# SimpleLedEgg.net
KiCad netlist of a schematic drawn in EAGLE
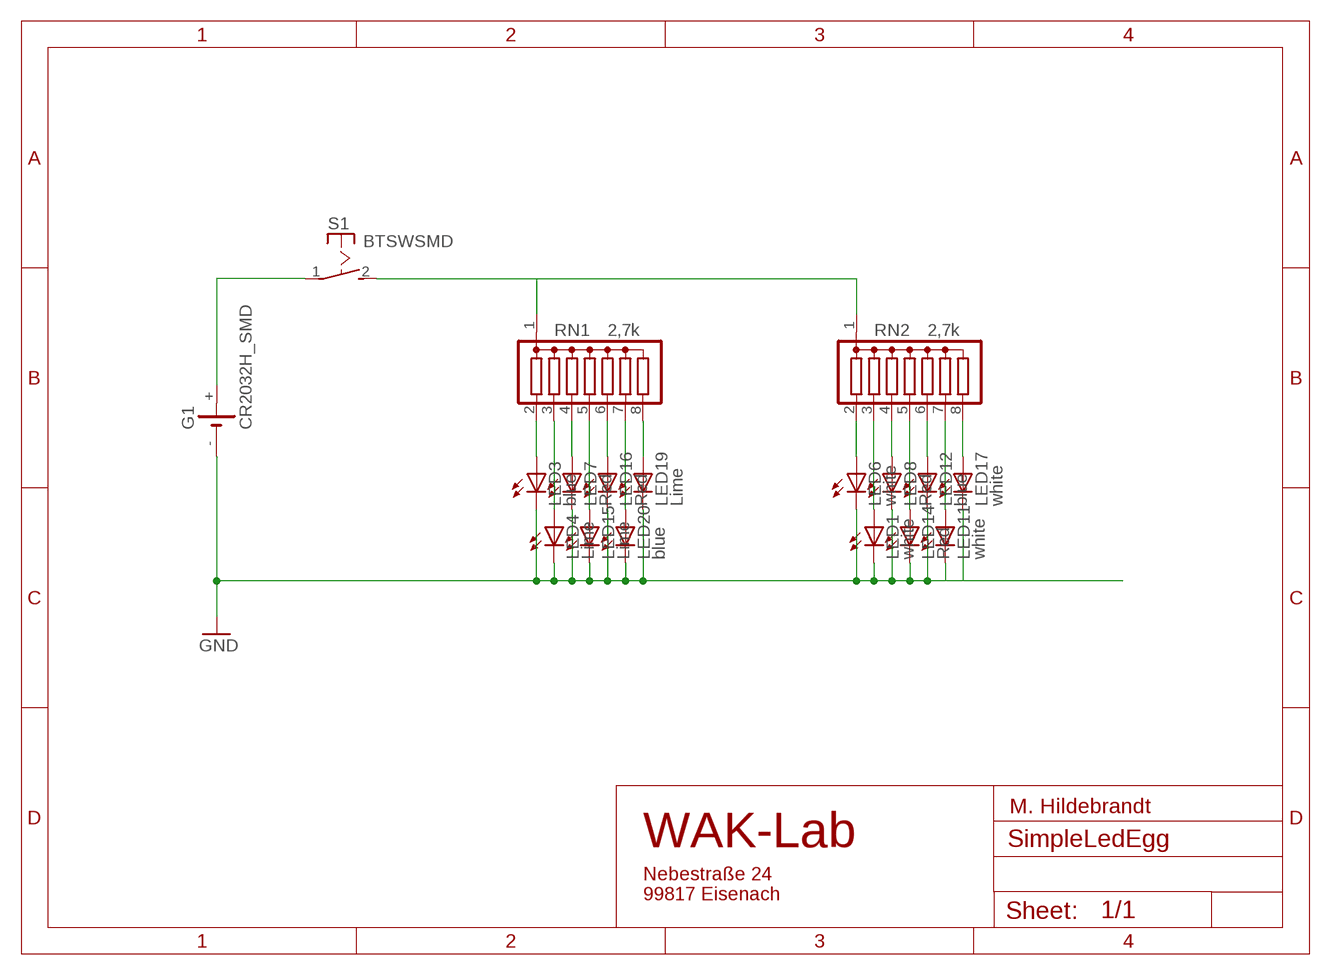
[diagram p0: schematic, sheet 1]

(export (version "E")
  (design (tool "Eeschema 10.0.6"))
  (components
    (comp (ref "G1")
      (value "CR2032H_SMD")
      (footprint "eagle-import:CR2032H_SMD")
      (libsource (lib "eagle-import") (part "CR2032H_SMD"))
    )
    (comp (ref "LED1")
      (value "white")
      (footprint "eagle-import:LED3MM")
      (libsource (lib "eagle-import") (part "LED3MM"))
    )
    (comp (ref "LED3")
      (value "blue")
      (footprint "eagle-import:LED3MM")
      (libsource (lib "eagle-import") (part "LED3MM"))
    )
    (comp (ref "LED4")
      (value "Lime")
      (footprint "eagle-import:LED3MM")
      (libsource (lib "eagle-import") (part "LED3MM"))
    )
    (comp (ref "LED6")
      (value "white")
      (footprint "eagle-import:LED3MM")
      (libsource (lib "eagle-import") (part "LED3MM"))
    )
    (comp (ref "LED7")
      (value "Red")
      (footprint "eagle-import:LED3MM")
      (libsource (lib "eagle-import") (part "LED3MM"))
    )
    (comp (ref "LED8")
      (value "Red")
      (footprint "eagle-import:LED3MM")
      (libsource (lib "eagle-import") (part "LED3MM"))
    )
    (comp (ref "LED11")
      (value "white")
      (footprint "eagle-import:LED3MM")
      (libsource (lib "eagle-import") (part "LED3MM"))
    )
    (comp (ref "LED12")
      (value "blue")
      (footprint "eagle-import:LED3MM")
      (libsource (lib "eagle-import") (part "LED3MM"))
    )
    (comp (ref "LED14")
      (value "Red")
      (footprint "eagle-import:LED3MM")
      (libsource (lib "eagle-import") (part "LED3MM"))
    )
    (comp (ref "LED15")
      (value "Lime")
      (footprint "eagle-import:LED3MM")
      (libsource (lib "eagle-import") (part "LED3MM"))
    )
    (comp (ref "LED16")
      (value "Red")
      (footprint "eagle-import:LED3MM")
      (libsource (lib "eagle-import") (part "LED3MM"))
    )
    (comp (ref "LED17")
      (value "white")
      (footprint "eagle-import:LED3MM")
      (libsource (lib "eagle-import") (part "LED3MM"))
    )
    (comp (ref "LED19")
      (value "Lime")
      (footprint "eagle-import:LED3MM")
      (libsource (lib "eagle-import") (part "LED3MM"))
    )
    (comp (ref "LED20")
      (value "blue")
      (footprint "eagle-import:LED3MM")
      (libsource (lib "eagle-import") (part "LED3MM"))
    )
    (comp (ref "RN1")
      (value "2,7k")
      (footprint "eagle-import:SIL8")
      (libsource (lib "eagle-import") (part "G07R"))
    )
    (comp (ref "RN2")
      (value "2,7k")
      (footprint "eagle-import:SIL8")
      (libsource (lib "eagle-import") (part "G07R"))
    )
    (comp (ref "S1")
      (value "BTSWSMD")
      (footprint "eagle-import:BTSW_SMD")
      (libsource (lib "eagle-import") (part "BTSWSMD"))
    )
  )
  (nets
    (net (code "1") (name "GND") (class "Default")
      (node (ref "G1") (pin "-") (pinfunction "-_-") (pintype "passive"))
      (node (ref "LED1") (pin "K") (pinfunction "C_K") (pintype "passive"))
      (node (ref "LED11") (pin "K") (pinfunction "C_K") (pintype "passive"))
      (node (ref "LED12") (pin "K") (pinfunction "C_K") (pintype "passive"))
      (node (ref "LED14") (pin "K") (pinfunction "C_K") (pintype "passive"))
      (node (ref "LED15") (pin "K") (pinfunction "C_K") (pintype "passive"))
      (node (ref "LED16") (pin "K") (pinfunction "C_K") (pintype "passive"))
      (node (ref "LED17") (pin "K") (pinfunction "C_K") (pintype "passive"))
      (node (ref "LED19") (pin "K") (pinfunction "C_K") (pintype "passive"))
      (node (ref "LED20") (pin "K") (pinfunction "C_K") (pintype "passive"))
      (node (ref "LED3") (pin "K") (pinfunction "C_K") (pintype "passive"))
      (node (ref "LED4") (pin "K") (pinfunction "C_K") (pintype "passive"))
      (node (ref "LED6") (pin "K") (pinfunction "C_K") (pintype "passive"))
      (node (ref "LED7") (pin "K") (pinfunction "C_K") (pintype "passive"))
      (node (ref "LED8") (pin "K") (pinfunction "C_K") (pintype "passive"))
    )
    (net (code "2") (name "Net-(LED1-PadA)") (class "Default")
      (node (ref "LED1") (pin "A") (pinfunction "A_A") (pintype "passive"))
      (node (ref "RN2") (pin "3") (pinfunction "3_3") (pintype "passive"))
    )
    (net (code "3") (name "Net-(LED3-PadA)") (class "Default")
      (node (ref "LED3") (pin "A") (pinfunction "A_A") (pintype "passive"))
      (node (ref "RN1") (pin "2") (pinfunction "2_2") (pintype "passive"))
    )
    (net (code "4") (name "Net-(LED4-PadA)") (class "Default")
      (node (ref "LED4") (pin "A") (pinfunction "A_A") (pintype "passive"))
      (node (ref "RN1") (pin "3") (pinfunction "3_3") (pintype "passive"))
    )
    (net (code "5") (name "Net-(LED6-PadA)") (class "Default")
      (node (ref "LED6") (pin "A") (pinfunction "A_A") (pintype "passive"))
      (node (ref "RN2") (pin "2") (pinfunction "2_2") (pintype "passive"))
    )
    (net (code "6") (name "Net-(LED7-PadA)") (class "Default")
      (node (ref "LED7") (pin "A") (pinfunction "A_A") (pintype "passive"))
      (node (ref "RN1") (pin "4") (pinfunction "4_4") (pintype "passive"))
    )
    (net (code "7") (name "Net-(LED8-PadA)") (class "Default")
      (node (ref "LED8") (pin "A") (pinfunction "A_A") (pintype "passive"))
      (node (ref "RN2") (pin "4") (pinfunction "4_4") (pintype "passive"))
    )
    (net (code "8") (name "Net-(LED11-PadA)") (class "Default")
      (node (ref "LED11") (pin "A") (pinfunction "A_A") (pintype "passive"))
      (node (ref "RN2") (pin "7") (pinfunction "7_7") (pintype "passive"))
    )
    (net (code "9") (name "Net-(LED12-PadA)") (class "Default")
      (node (ref "LED12") (pin "A") (pinfunction "A_A") (pintype "passive"))
      (node (ref "RN2") (pin "6") (pinfunction "6_6") (pintype "passive"))
    )
    (net (code "10") (name "Net-(LED14-PadA)") (class "Default")
      (node (ref "LED14") (pin "A") (pinfunction "A_A") (pintype "passive"))
      (node (ref "RN2") (pin "5") (pinfunction "5_5") (pintype "passive"))
    )
    (net (code "11") (name "Net-(LED15-PadA)") (class "Default")
      (node (ref "LED15") (pin "A") (pinfunction "A_A") (pintype "passive"))
      (node (ref "RN1") (pin "5") (pinfunction "5_5") (pintype "passive"))
    )
    (net (code "12") (name "Net-(LED16-PadA)") (class "Default")
      (node (ref "LED16") (pin "A") (pinfunction "A_A") (pintype "passive"))
      (node (ref "RN1") (pin "6") (pinfunction "6_6") (pintype "passive"))
    )
    (net (code "13") (name "Net-(LED17-PadA)") (class "Default")
      (node (ref "LED17") (pin "A") (pinfunction "A_A") (pintype "passive"))
      (node (ref "RN2") (pin "8") (pinfunction "8_8") (pintype "passive"))
    )
    (net (code "14") (name "Net-(LED19-PadA)") (class "Default")
      (node (ref "LED19") (pin "A") (pinfunction "A_A") (pintype "passive"))
      (node (ref "RN1") (pin "8") (pinfunction "8_8") (pintype "passive"))
    )
    (net (code "15") (name "Net-(LED20-PadA)") (class "Default")
      (node (ref "LED20") (pin "A") (pinfunction "A_A") (pintype "passive"))
      (node (ref "RN1") (pin "7") (pinfunction "7_7") (pintype "passive"))
    )
    (net (code "16") (name "Net-(S1-P)") (class "Default")
      (node (ref "G1") (pin "+") (pinfunction "+_+") (pintype "passive"))
      (node (ref "S1") (pin "1") (pinfunction "P_1") (pintype "passive"))
    )
    (net (code "17") (name "Net-(S1-S)") (class "Default")
      (node (ref "RN1") (pin "1") (pinfunction "1_1") (pintype "passive"))
      (node (ref "RN2") (pin "1") (pinfunction "1_1") (pintype "passive"))
      (node (ref "S1") (pin "2") (pinfunction "S_2") (pintype "passive"))
    )
  )
)
